# 5_SWD_schdoc.net
KiCad netlist of a schematic drawn in Altium Designer
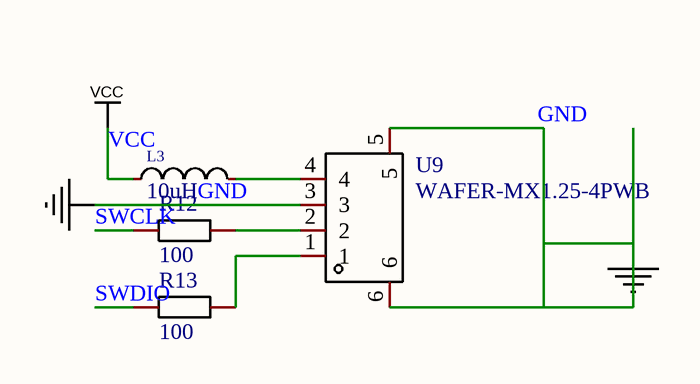
[diagram p0: 5_SWD.schdoc.schdoc]

(export (version "E")
  (design (tool "Eeschema 10.0.6"))
  (components
    (comp (ref "L3")
      (value "10uH")
      (fields
        (field (name "NAME") "10uH")
        (field (name "MANUFACTURER") "Sunlord(顺络)")
        (field (name "MANUFACTURER PART") "SDFL1608S100KTF")
      )
      (libsource (lib "altium-import") (part "root_0_L_0603_"))
    )
    (comp (ref "R12")
      (value "100")
      (fields (field (name "NAME") "100"))
      (libsource (lib "altium-import") (part "root_0_Res_0603_"))
    )
    (comp (ref "R13")
      (value "100")
      (fields (field (name "NAME") "100"))
      (libsource (lib "altium-import") (part "root_0_Res_0603_"))
    )
    (comp (ref "U9")
      (value "WAFER-MX1.25-4PWB")
      (description "插针结构:1x4P;间距:1.25mm;公母:公;安装方式:卧贴;排数:1;每排PIN数:4;额定电流:1A;工作温度范围:-25℃~+85℃;")
      (fields (field (name "NAME") "WAFER-MX1.25-4PWB") (field (name "MANUFACTURER") "XUNPU(讯普)"))
      (libsource (lib "altium-import") (part "root_2_mirrored_WAFER-MX1.25-4PWB_"))
    )
  )
  (nets
    (net (code "1") (name "/GND") (class "Default")
      (node (ref "U9") (pin "3") (pinfunction "3_3") (pintype "passive"))
      (node (ref "U9") (pin "5") (pinfunction "5_5") (pintype "passive"))
      (node (ref "U9") (pin "6") (pinfunction "6_6") (pintype "passive"))
    )
    (net (code "2") (name "/SWCLK") (class "Default")
      (node (ref "R12") (pin "1") (pinfunction "1_1") (pintype "passive"))
    )
    (net (code "3") (name "/SWDIO") (class "Default")
      (node (ref "R13") (pin "1") (pinfunction "1_1") (pintype "passive"))
    )
    (net (code "4") (name "Net-(L3-Pad2)") (class "Default")
      (node (ref "L3") (pin "2") (pinfunction "2_2") (pintype "passive"))
      (node (ref "U9") (pin "4") (pinfunction "4_4") (pintype "passive"))
    )
    (net (code "5") (name "Net-(R12-Pad2)") (class "Default")
      (node (ref "R12") (pin "2") (pinfunction "2_2") (pintype "passive"))
      (node (ref "U9") (pin "2") (pinfunction "2_2") (pintype "passive"))
    )
    (net (code "6") (name "Net-(R13-Pad2)") (class "Default")
      (node (ref "R13") (pin "2") (pinfunction "2_2") (pintype "passive"))
      (node (ref "U9") (pin "1") (pinfunction "1_1") (pintype "passive"))
    )
    (net (code "7") (name "VCC") (class "Default")
      (node (ref "L3") (pin "1") (pinfunction "1_1") (pintype "passive"))
    )
  )
)
